# Qwiic_TMP117.net
KiCad netlist of a schematic drawn in EAGLE
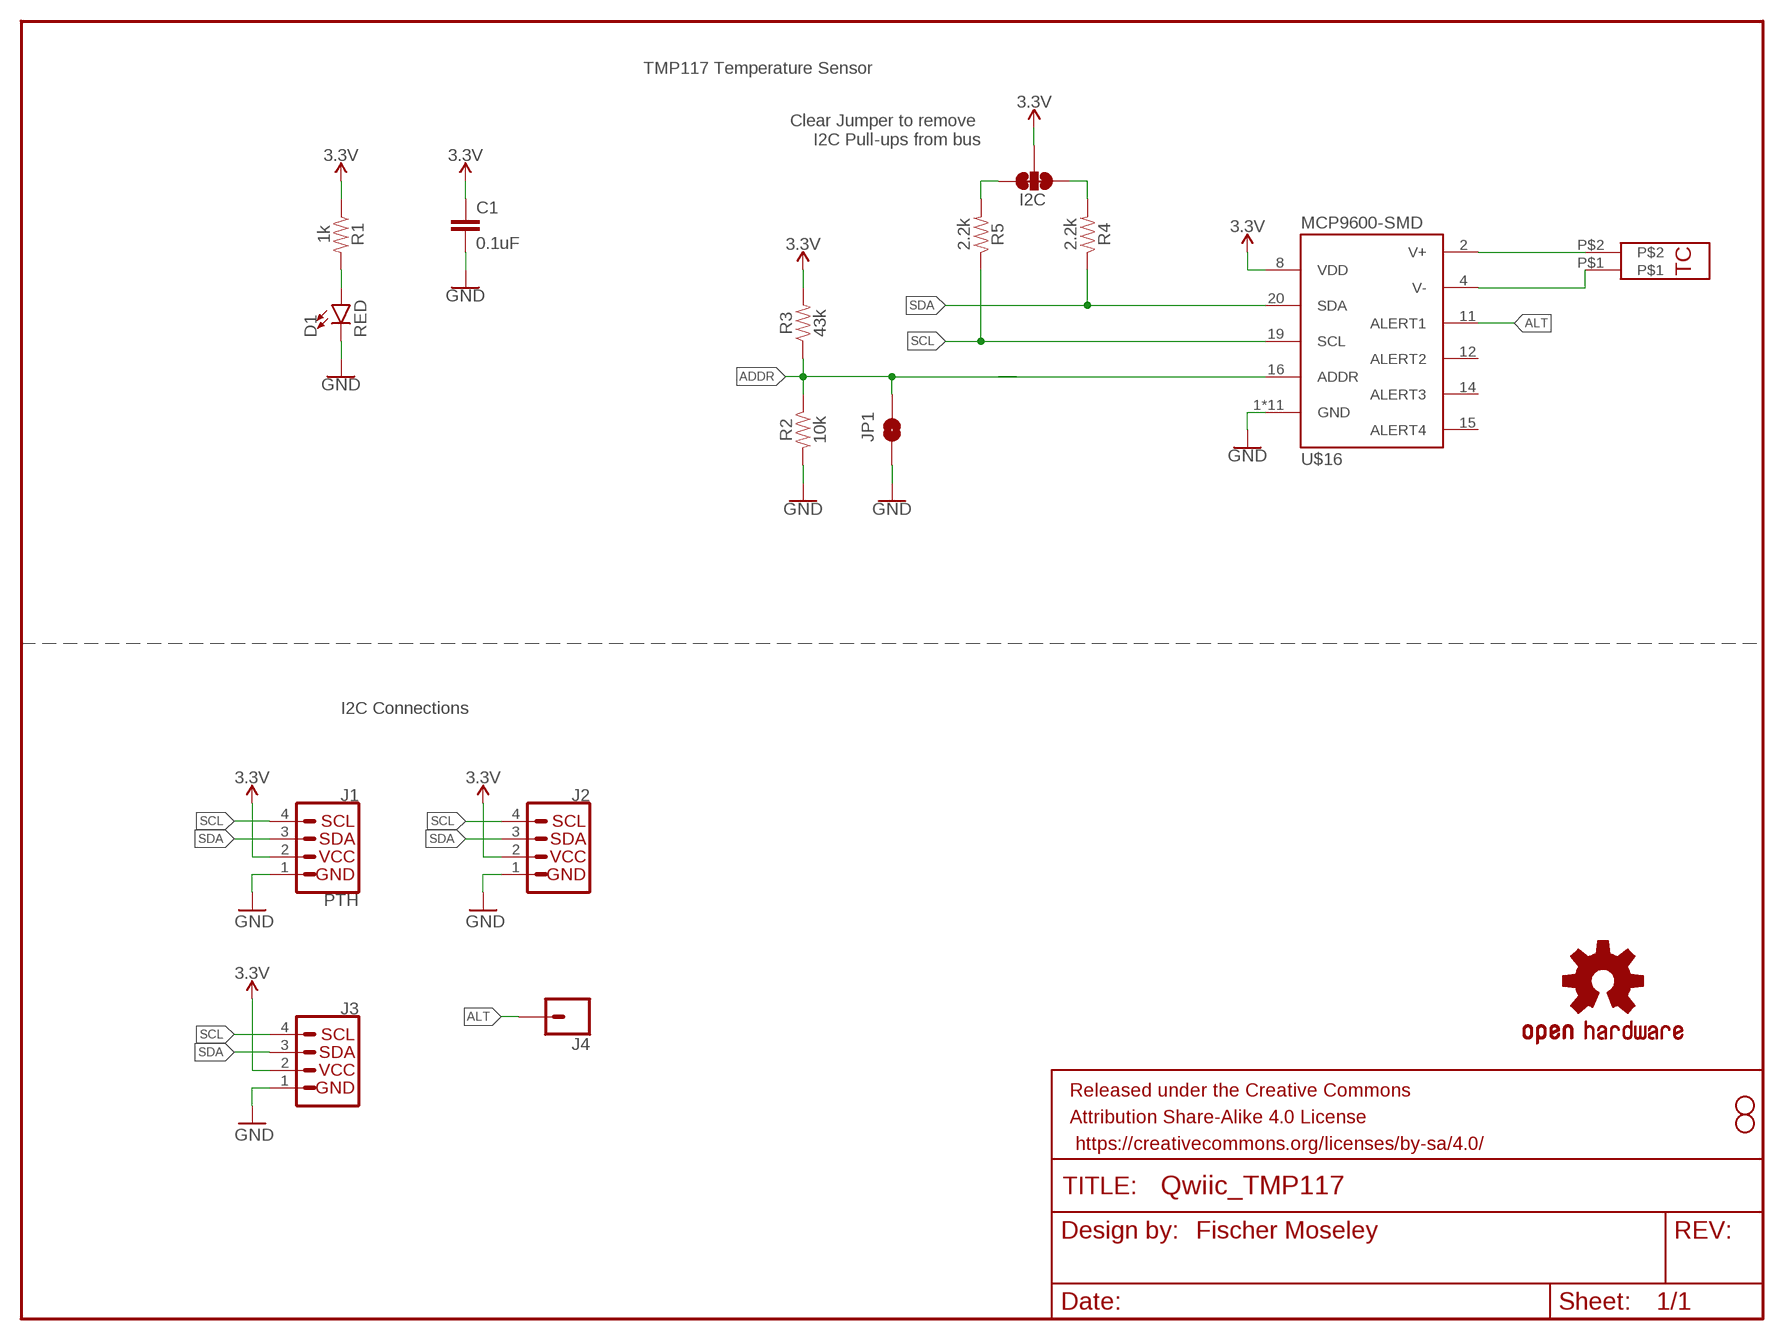
[diagram p0: schematic, sheet 1]

(export (version "E")
  (design (tool "Eeschema 10.0.6"))
  (components
    (comp (ref "C1")
      (value "0.1uF")
      (footprint "eagle-import:0603")
      (libsource (lib "eagle-import") (part "0.1UF-0603-25V-(+80/-20%)"))
    )
    (comp (ref "D1")
      (value "RED")
      (footprint "eagle-import:LED-0603")
      (libsource (lib "eagle-import") (part "LED-RED0603"))
    )
    (comp (ref "FRAME1")
      (value "FRAME-LETTER")
      (footprint "eagle-import:CREATIVE_COMMONS")
      (libsource (lib "eagle-import") (part "FRAME-LETTER"))
    )
    (comp (ref "I2C")
      (value "JUMPER-SMT_3_2-NC_TRACE_SILK")
      (footprint "eagle-import:SMT-JUMPER_3_2-NC_TRACE_SILK")
      (libsource (lib "eagle-import") (part "JUMPER-SMT_3_2-NC_TRACE_SILK"))
    )
    (comp (ref "J1")
      (value "PTH")
      (footprint "eagle-import:1X04_NO_SILK")
      (libsource (lib "eagle-import") (part "I2C_STANDARD_NO_SILK"))
    )
    (comp (ref "J2")
      (value "QWIIC_CONNECTORJS-1MM")
      (footprint "eagle-import:JST04_1MM_RA")
      (libsource (lib "eagle-import") (part "QWIIC_CONNECTORJS-1MM"))
    )
    (comp (ref "J3")
      (value "QWIIC_CONNECTORJS-1MM")
      (footprint "eagle-import:JST04_1MM_RA")
      (libsource (lib "eagle-import") (part "QWIIC_CONNECTORJS-1MM"))
    )
    (comp (ref "J4")
      (value "CONN_01PTH_NO_SILK_YES_STOP")
      (footprint "eagle-import:1X01_NO_SILK")
      (libsource (lib "eagle-import") (part "CONN_01PTH_NO_SILK_YES_STOP"))
    )
    (comp (ref "JP1")
      (value "JUMPER-SMT_2_NO_SILK")
      (footprint "eagle-import:SMT-JUMPER_2_NO_SILK")
      (libsource (lib "eagle-import") (part "JUMPER-SMT_2_NO_SILK"))
    )
    (comp (ref "JP8")
      (value "STAND-OFF")
      (footprint "eagle-import:STAND-OFF")
      (libsource (lib "eagle-import") (part "STAND-OFF"))
    )
    (comp (ref "JP9")
      (value "STAND-OFF")
      (footprint "eagle-import:STAND-OFF")
      (libsource (lib "eagle-import") (part "STAND-OFF"))
    )
    (comp (ref "LOGO1")
      (value "OSHW-LOGOMINI")
      (footprint "eagle-import:OSHW-LOGO-MINI")
      (libsource (lib "eagle-import") (part "OSHW-LOGOMINI"))
    )
    (comp (ref "R1")
      (value "1k")
      (footprint "eagle-import:0603")
      (libsource (lib "eagle-import") (part "1KOHM-0603-1/10W-1%"))
    )
    (comp (ref "R2")
      (value "10k")
      (footprint "eagle-import:0603")
      (libsource (lib "eagle-import") (part "10KOHM-0603-1/10W-1%"))
    )
    (comp (ref "R3")
      (value "43k")
      (footprint "eagle-import:0603")
      (libsource (lib "eagle-import") (part "43KOHM-0603-1/10W-1%"))
    )
    (comp (ref "R4")
      (value "2.2k")
      (footprint "eagle-import:0603")
      (libsource (lib "eagle-import") (part "2.2KOHM-0603-1/10W-1%"))
    )
    (comp (ref "R5")
      (value "2.2k")
      (footprint "eagle-import:0603")
      (libsource (lib "eagle-import") (part "2.2KOHM-0603-1/10W-1%"))
    )
    (comp (ref "U$16")
      (value "MCP9600-SMD")
      (footprint "eagle-import:MQFN-20")
      (libsource (lib "eagle-import") (part "MCP9600-SMD"))
    )
    (comp (ref "U$24")
      (value "CHARLESPAX_TC-MINI-CONNECTOR")
      (footprint "eagle-import:CHARLESPAX_TC-MINI-CONNECTOR")
      (libsource (lib "eagle-import") (part "CHARLESPAX_TC-MINI-CONNECTOR"))
    )
  )
  (nets
    (net (code "1") (name "3.3V") (class "Default")
      (node (ref "C1") (pin "1") (pinfunction "1_1") (pintype "passive"))
      (node (ref "I2C") (pin "2") (pinfunction "2_2") (pintype "passive"))
      (node (ref "J1") (pin "2") (pinfunction "VCC_2") (pintype "power_in"))
      (node (ref "J2") (pin "2") (pinfunction "2_2") (pintype "power_in"))
      (node (ref "J3") (pin "2") (pinfunction "2_2") (pintype "power_in"))
      (node (ref "R1") (pin "1") (pinfunction "1_1") (pintype "passive"))
      (node (ref "R3") (pin "2") (pinfunction "2_2") (pintype "passive"))
      (node (ref "U$16") (pin "8") (pinfunction "VDD_8") (pintype "bidirectional"))
    )
    (net (code "2") (name "ADDR") (class "Default")
      (node (ref "JP1") (pin "1") (pinfunction "1_1") (pintype "passive"))
      (node (ref "R2") (pin "1") (pinfunction "1_1") (pintype "passive"))
      (node (ref "R3") (pin "1") (pinfunction "1_1") (pintype "passive"))
      (node (ref "U$16") (pin "16") (pinfunction "ADDR_16") (pintype "bidirectional"))
    )
    (net (code "3") (name "ALT") (class "Default")
      (node (ref "J4") (pin "1") (pinfunction "1_1") (pintype "passive"))
      (node (ref "U$16") (pin "11") (pinfunction "ALERT1_11") (pintype "bidirectional"))
    )
    (net (code "4") (name "GND") (class "Default")
      (node (ref "C1") (pin "2") (pinfunction "2_2") (pintype "passive"))
      (node (ref "D1") (pin "C") (pinfunction "C_C") (pintype "passive"))
      (node (ref "J1") (pin "1") (pinfunction "GND_1") (pintype "power_in"))
      (node (ref "J2") (pin "1") (pinfunction "1_1") (pintype "power_in"))
      (node (ref "J3") (pin "1") (pinfunction "1_1") (pintype "power_in"))
      (node (ref "JP1") (pin "2") (pinfunction "2_2") (pintype "passive"))
      (node (ref "R2") (pin "2") (pinfunction "2_2") (pintype "passive"))
      (node (ref "U$16") (pin "1") (pinfunction "GND_1") (pintype "bidirectional"))
      (node (ref "U$16") (pin "10") (pinfunction "GND_10") (pintype "bidirectional"))
      (node (ref "U$16") (pin "13") (pinfunction "GND_13") (pintype "bidirectional"))
      (node (ref "U$16") (pin "17") (pinfunction "GND_17") (pintype "bidirectional"))
      (node (ref "U$16") (pin "18") (pinfunction "GND_18") (pintype "bidirectional"))
      (node (ref "U$16") (pin "21") (pinfunction "GND_21") (pintype "bidirectional"))
      (node (ref "U$16") (pin "3") (pinfunction "GND_3") (pintype "bidirectional"))
      (node (ref "U$16") (pin "5") (pinfunction "GND_5") (pintype "bidirectional"))
      (node (ref "U$16") (pin "6") (pinfunction "GND_6") (pintype "bidirectional"))
      (node (ref "U$16") (pin "7") (pinfunction "GND_7") (pintype "bidirectional"))
      (node (ref "U$16") (pin "9") (pinfunction "GND_9") (pintype "bidirectional"))
    )
    (net (code "5") (name "Net-(D1-PadA)") (class "Default")
      (node (ref "D1") (pin "A") (pinfunction "A_A") (pintype "passive"))
      (node (ref "R1") (pin "2") (pinfunction "2_2") (pintype "passive"))
    )
    (net (code "6") (name "Net-(I2C-Pad1)") (class "Default")
      (node (ref "I2C") (pin "1") (pinfunction "1_1") (pintype "passive"))
      (node (ref "R5") (pin "2") (pinfunction "2_2") (pintype "passive"))
    )
    (net (code "7") (name "Net-(I2C-Pad3)") (class "Default")
      (node (ref "I2C") (pin "3") (pinfunction "3_3") (pintype "passive"))
      (node (ref "R4") (pin "2") (pinfunction "2_2") (pintype "passive"))
    )
    (net (code "8") (name "Net-(U$16-V+)") (class "Default")
      (node (ref "U$16") (pin "2") (pinfunction "V+_2") (pintype "bidirectional"))
      (node (ref "U$24") (pin "P$2") (pinfunction "P$2_P$2") (pintype "bidirectional"))
    )
    (net (code "9") (name "Net-(U$16-V-)") (class "Default")
      (node (ref "U$16") (pin "4") (pinfunction "V-_4") (pintype "bidirectional"))
      (node (ref "U$24") (pin "P$1") (pinfunction "P$1_P$1") (pintype "bidirectional"))
    )
    (net (code "10") (name "SCL") (class "Default")
      (node (ref "J1") (pin "4") (pinfunction "SCL_4") (pintype "passive"))
      (node (ref "J2") (pin "4") (pinfunction "4_4") (pintype "passive"))
      (node (ref "J3") (pin "4") (pinfunction "4_4") (pintype "passive"))
      (node (ref "R5") (pin "1") (pinfunction "1_1") (pintype "passive"))
      (node (ref "U$16") (pin "19") (pinfunction "SCL_19") (pintype "bidirectional"))
    )
    (net (code "11") (name "SDA") (class "Default")
      (node (ref "J1") (pin "3") (pinfunction "SDA_3") (pintype "passive"))
      (node (ref "J2") (pin "3") (pinfunction "3_3") (pintype "passive"))
      (node (ref "J3") (pin "3") (pinfunction "3_3") (pintype "passive"))
      (node (ref "R4") (pin "1") (pinfunction "1_1") (pintype "passive"))
      (node (ref "U$16") (pin "20") (pinfunction "SDA_20") (pintype "bidirectional"))
    )
    (net (code "12") (name "unconnected-(U$16-ALERT2-Pad12)") (class "Default")
      (node (ref "U$16") (pin "12") (pinfunction "ALERT2_12") (pintype "bidirectional"))
    )
    (net (code "13") (name "unconnected-(U$16-ALERT3-Pad14)") (class "Default")
      (node (ref "U$16") (pin "14") (pinfunction "ALERT3_14") (pintype "bidirectional"))
    )
    (net (code "14") (name "unconnected-(U$16-ALERT4-Pad15)") (class "Default")
      (node (ref "U$16") (pin "15") (pinfunction "ALERT4_15") (pintype "bidirectional"))
    )
  )
)
